# servo-pwm.net
KiCad netlist of a schematic drawn in EAGLE
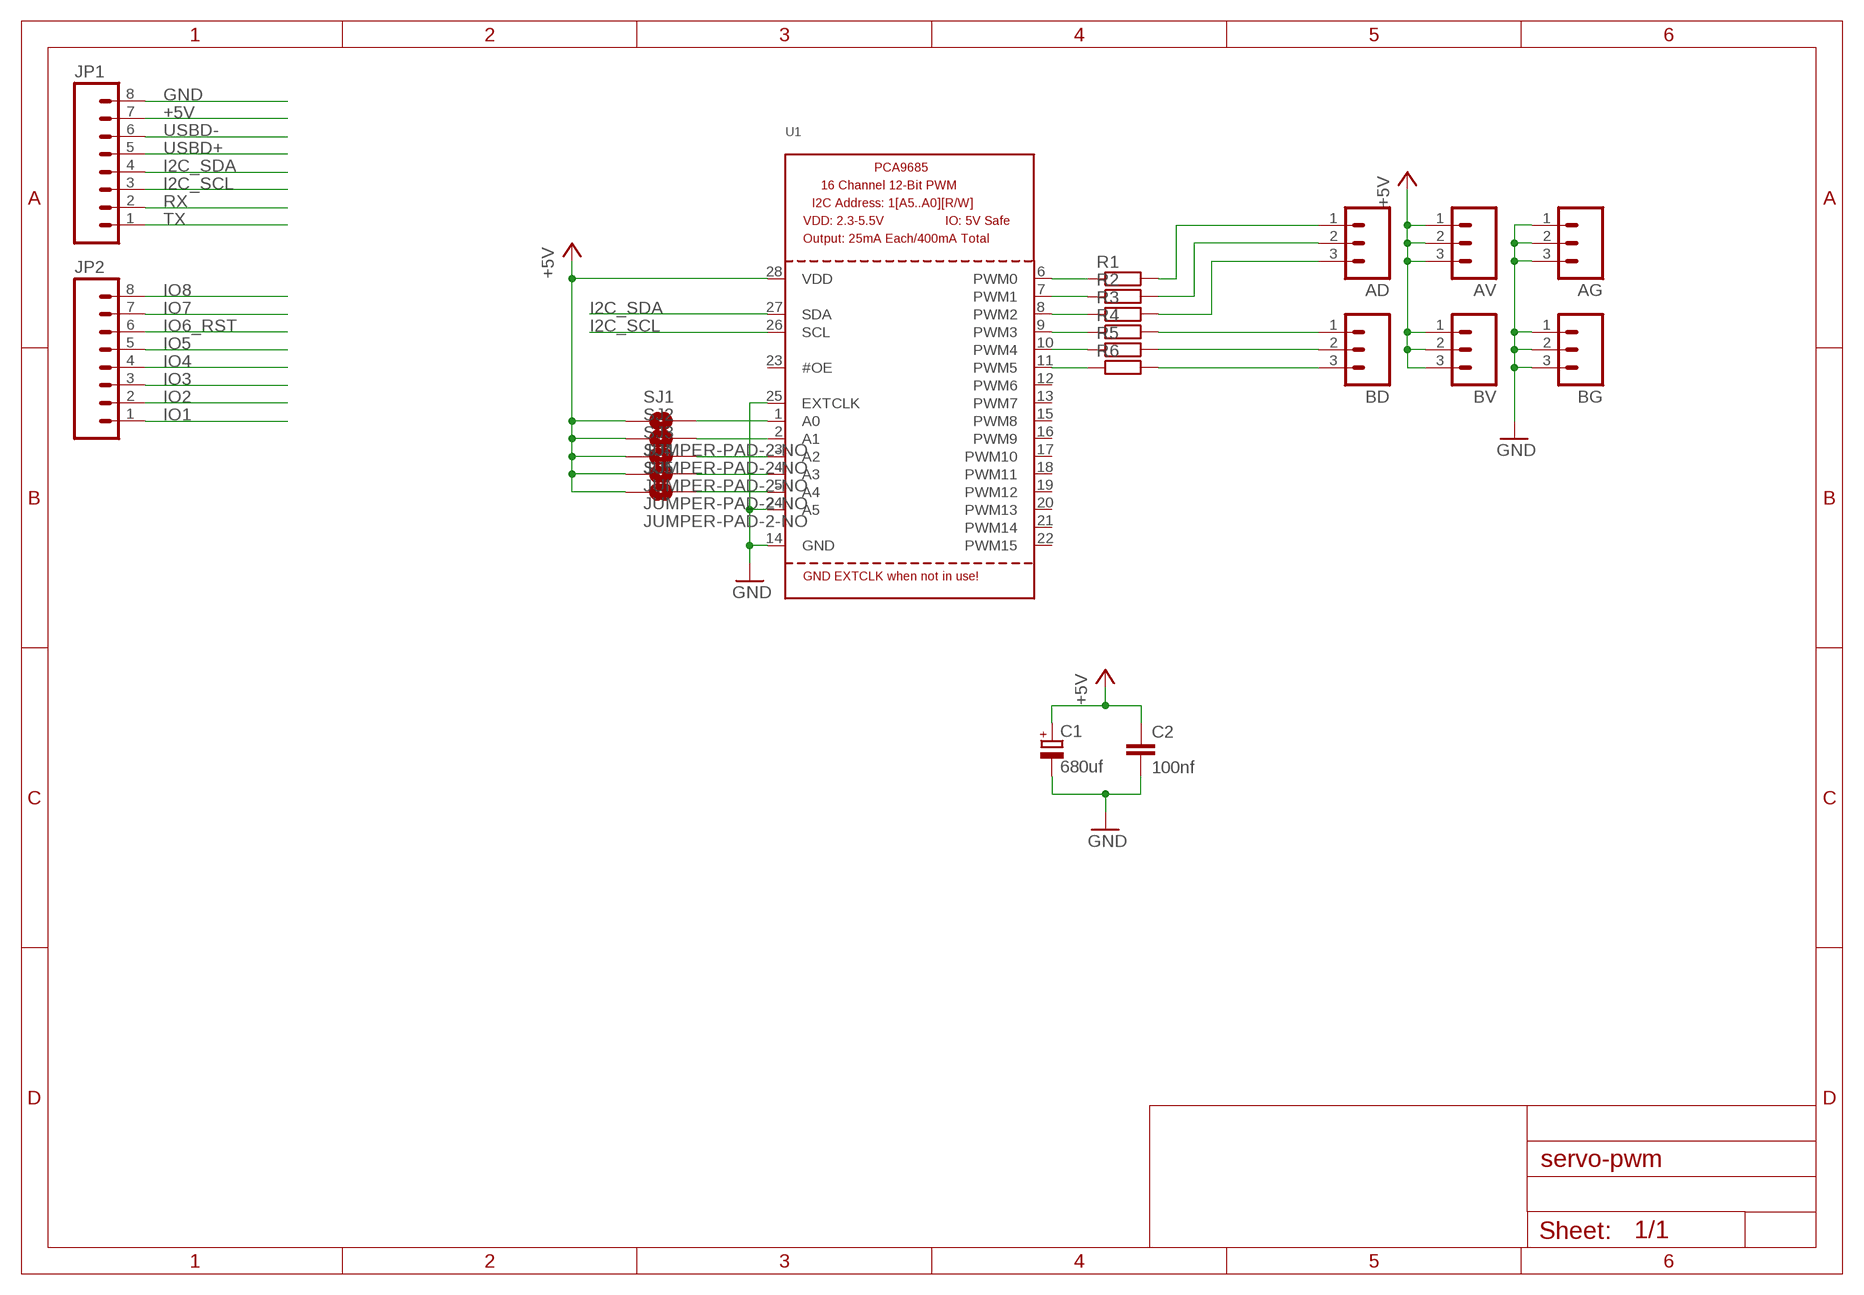
[diagram p0: schematic, sheet 1]

(export (version "E")
  (design (tool "Eeschema 10.0.6"))
  (components
    (comp (ref "AD")
      (value "M03LOCK")
      (footprint "eagle-import:1X03_LOCK")
      (libsource (lib "eagle-import") (part "M03LOCK"))
    )
    (comp (ref "AG")
      (value "M03LOCK")
      (footprint "eagle-import:1X03_LOCK")
      (libsource (lib "eagle-import") (part "M03LOCK"))
    )
    (comp (ref "AV")
      (value "M03LOCK")
      (footprint "eagle-import:1X03_LOCK")
      (libsource (lib "eagle-import") (part "M03LOCK"))
    )
    (comp (ref "BD")
      (value "M03LOCK")
      (footprint "eagle-import:1X03_LOCK")
      (libsource (lib "eagle-import") (part "M03LOCK"))
    )
    (comp (ref "BG")
      (value "M03LOCK")
      (footprint "eagle-import:1X03_LOCK")
      (libsource (lib "eagle-import") (part "M03LOCK"))
    )
    (comp (ref "BV")
      (value "M03LOCK")
      (footprint "eagle-import:1X03_LOCK")
      (libsource (lib "eagle-import") (part "M03LOCK"))
    )
    (comp (ref "C1")
      (value "680uf")
      (footprint "eagle-import:E2,5-7")
      (libsource (lib "eagle-import") (part "CPOL-EUE2.5-7"))
    )
    (comp (ref "C2")
      (value "100nf")
      (footprint "eagle-import:C025-030X050")
      (libsource (lib "eagle-import") (part "C-EU025-030X050"))
    )
    (comp (ref "JP1")
      (value "M081X08")
      (footprint "eagle-import:1X08")
      (libsource (lib "eagle-import") (part "M081X08"))
    )
    (comp (ref "JP2")
      (value "M081X08")
      (footprint "eagle-import:1X08")
      (libsource (lib "eagle-import") (part "M081X08"))
    )
    (comp (ref "R1")
      (value "R-EU_M0805")
      (footprint "eagle-import:M0805")
      (libsource (lib "eagle-import") (part "R-EU_M0805"))
    )
    (comp (ref "R2")
      (value "R-EU_M0805")
      (footprint "eagle-import:M0805")
      (libsource (lib "eagle-import") (part "R-EU_M0805"))
    )
    (comp (ref "R3")
      (value "R-EU_M0805")
      (footprint "eagle-import:M0805")
      (libsource (lib "eagle-import") (part "R-EU_M0805"))
    )
    (comp (ref "R4")
      (value "R-EU_M0805")
      (footprint "eagle-import:M0805")
      (libsource (lib "eagle-import") (part "R-EU_M0805"))
    )
    (comp (ref "R5")
      (value "R-EU_M0805")
      (footprint "eagle-import:M0805")
      (libsource (lib "eagle-import") (part "R-EU_M0805"))
    )
    (comp (ref "R6")
      (value "R-EU_M0805")
      (footprint "eagle-import:M0805")
      (libsource (lib "eagle-import") (part "R-EU_M0805"))
    )
    (comp (ref "SJ1")
      (value "JUMPER-PAD-2-NO")
      (footprint "eagle-import:PAD-JUMPER-2-NO_NO_SILK")
      (libsource (lib "eagle-import") (part "JUMPER-PAD-2-NO"))
    )
    (comp (ref "SJ2")
      (value "JUMPER-PAD-2-NO")
      (footprint "eagle-import:PAD-JUMPER-2-NO_NO_SILK")
      (libsource (lib "eagle-import") (part "JUMPER-PAD-2-NO"))
    )
    (comp (ref "SJ3")
      (value "JUMPER-PAD-2-NO")
      (footprint "eagle-import:PAD-JUMPER-2-NO_NO_SILK")
      (libsource (lib "eagle-import") (part "JUMPER-PAD-2-NO"))
    )
    (comp (ref "SJ4")
      (value "JUMPER-PAD-2-NO")
      (footprint "eagle-import:PAD-JUMPER-2-NO_NO_SILK")
      (libsource (lib "eagle-import") (part "JUMPER-PAD-2-NO"))
    )
    (comp (ref "SJ5")
      (value "JUMPER-PAD-2-NO")
      (footprint "eagle-import:PAD-JUMPER-2-NO_NO_SILK")
      (libsource (lib "eagle-import") (part "JUMPER-PAD-2-NO"))
    )
    (comp (ref "U1")
      (value "PCA9685")
      (footprint "eagle-import:TSSOP28")
      (libsource (lib "eagle-import") (part "PCA9685"))
    )
  )
  (nets
    (net (code "1") (name "+5V") (class "Default")
      (node (ref "AV") (pin "1") (pinfunction "1_1") (pintype "passive"))
      (node (ref "AV") (pin "2") (pinfunction "2_2") (pintype "passive"))
      (node (ref "AV") (pin "3") (pinfunction "3_3") (pintype "passive"))
      (node (ref "BV") (pin "1") (pinfunction "1_1") (pintype "passive"))
      (node (ref "BV") (pin "2") (pinfunction "2_2") (pintype "passive"))
      (node (ref "BV") (pin "3") (pinfunction "3_3") (pintype "passive"))
      (node (ref "C1") (pin "+") (pinfunction "+_+") (pintype "passive"))
      (node (ref "C2") (pin "1") (pinfunction "1_1") (pintype "passive"))
      (node (ref "JP1") (pin "7") (pinfunction "7_7") (pintype "passive"))
      (node (ref "SJ1") (pin "1") (pinfunction "1_1") (pintype "passive"))
      (node (ref "SJ2") (pin "1") (pinfunction "1_1") (pintype "passive"))
      (node (ref "SJ3") (pin "1") (pinfunction "1_1") (pintype "passive"))
      (node (ref "SJ4") (pin "1") (pinfunction "1_1") (pintype "passive"))
      (node (ref "SJ5") (pin "1") (pinfunction "1_1") (pintype "passive"))
      (node (ref "U1") (pin "28") (pinfunction "VDD_28") (pintype "power_in"))
    )
    (net (code "2") (name "/I2C_SCL") (class "Default")
      (node (ref "JP1") (pin "3") (pinfunction "3_3") (pintype "passive"))
      (node (ref "U1") (pin "26") (pinfunction "SCL_26") (pintype "bidirectional"))
    )
    (net (code "3") (name "/I2C_SDA") (class "Default")
      (node (ref "JP1") (pin "4") (pinfunction "4_4") (pintype "passive"))
      (node (ref "U1") (pin "27") (pinfunction "SDA_27") (pintype "bidirectional"))
    )
    (net (code "4") (name "/IO1") (class "Default")
      (node (ref "JP2") (pin "1") (pinfunction "1_1") (pintype "passive"))
    )
    (net (code "5") (name "/IO2") (class "Default")
      (node (ref "JP2") (pin "2") (pinfunction "2_2") (pintype "passive"))
    )
    (net (code "6") (name "/IO3") (class "Default")
      (node (ref "JP2") (pin "3") (pinfunction "3_3") (pintype "passive"))
    )
    (net (code "7") (name "/IO4") (class "Default")
      (node (ref "JP2") (pin "4") (pinfunction "4_4") (pintype "passive"))
    )
    (net (code "8") (name "/IO5") (class "Default")
      (node (ref "JP2") (pin "5") (pinfunction "5_5") (pintype "passive"))
    )
    (net (code "9") (name "/IO6_RST") (class "Default")
      (node (ref "JP2") (pin "6") (pinfunction "6_6") (pintype "passive"))
    )
    (net (code "10") (name "/IO7") (class "Default")
      (node (ref "JP2") (pin "7") (pinfunction "7_7") (pintype "passive"))
    )
    (net (code "11") (name "/IO8") (class "Default")
      (node (ref "JP2") (pin "8") (pinfunction "8_8") (pintype "passive"))
    )
    (net (code "12") (name "/RX") (class "Default")
      (node (ref "JP1") (pin "2") (pinfunction "2_2") (pintype "passive"))
    )
    (net (code "13") (name "/TX") (class "Default")
      (node (ref "JP1") (pin "1") (pinfunction "1_1") (pintype "passive"))
    )
    (net (code "14") (name "/USBD+") (class "Default")
      (node (ref "JP1") (pin "5") (pinfunction "5_5") (pintype "passive"))
    )
    (net (code "15") (name "/USBD-") (class "Default")
      (node (ref "JP1") (pin "6") (pinfunction "6_6") (pintype "passive"))
    )
    (net (code "16") (name "GND") (class "Default")
      (node (ref "AG") (pin "1") (pinfunction "1_1") (pintype "passive"))
      (node (ref "AG") (pin "2") (pinfunction "2_2") (pintype "passive"))
      (node (ref "AG") (pin "3") (pinfunction "3_3") (pintype "passive"))
      (node (ref "BG") (pin "1") (pinfunction "1_1") (pintype "passive"))
      (node (ref "BG") (pin "2") (pinfunction "2_2") (pintype "passive"))
      (node (ref "BG") (pin "3") (pinfunction "3_3") (pintype "passive"))
      (node (ref "C1") (pin "-") (pinfunction "-_-") (pintype "passive"))
      (node (ref "C2") (pin "2") (pinfunction "2_2") (pintype "passive"))
      (node (ref "JP1") (pin "8") (pinfunction "8_8") (pintype "passive"))
      (node (ref "U1") (pin "14") (pinfunction "GND_14") (pintype "power_in"))
      (node (ref "U1") (pin "24") (pinfunction "A5_24") (pintype "bidirectional"))
      (node (ref "U1") (pin "25") (pinfunction "EXTCLK_25") (pintype "input"))
    )
    (net (code "17") (name "Net-(AD-Pad1)") (class "Default")
      (node (ref "AD") (pin "1") (pinfunction "1_1") (pintype "passive"))
      (node (ref "R1") (pin "2") (pinfunction "2_2") (pintype "passive"))
    )
    (net (code "18") (name "Net-(AD-Pad2)") (class "Default")
      (node (ref "AD") (pin "2") (pinfunction "2_2") (pintype "passive"))
      (node (ref "R2") (pin "2") (pinfunction "2_2") (pintype "passive"))
    )
    (net (code "19") (name "Net-(AD-Pad3)") (class "Default")
      (node (ref "AD") (pin "3") (pinfunction "3_3") (pintype "passive"))
      (node (ref "R3") (pin "2") (pinfunction "2_2") (pintype "passive"))
    )
    (net (code "20") (name "Net-(BD-Pad1)") (class "Default")
      (node (ref "BD") (pin "1") (pinfunction "1_1") (pintype "passive"))
      (node (ref "R4") (pin "2") (pinfunction "2_2") (pintype "passive"))
    )
    (net (code "21") (name "Net-(BD-Pad2)") (class "Default")
      (node (ref "BD") (pin "2") (pinfunction "2_2") (pintype "passive"))
      (node (ref "R5") (pin "2") (pinfunction "2_2") (pintype "passive"))
    )
    (net (code "22") (name "Net-(BD-Pad3)") (class "Default")
      (node (ref "BD") (pin "3") (pinfunction "3_3") (pintype "passive"))
      (node (ref "R6") (pin "2") (pinfunction "2_2") (pintype "passive"))
    )
    (net (code "23") (name "Net-(U1-A0)") (class "Default")
      (node (ref "SJ1") (pin "2") (pinfunction "2_2") (pintype "passive"))
      (node (ref "U1") (pin "1") (pinfunction "A0_1") (pintype "bidirectional"))
    )
    (net (code "24") (name "Net-(U1-A1)") (class "Default")
      (node (ref "SJ2") (pin "2") (pinfunction "2_2") (pintype "passive"))
      (node (ref "U1") (pin "2") (pinfunction "A1_2") (pintype "bidirectional"))
    )
    (net (code "25") (name "Net-(U1-A2)") (class "Default")
      (node (ref "SJ3") (pin "2") (pinfunction "2_2") (pintype "passive"))
      (node (ref "U1") (pin "3") (pinfunction "A2_3") (pintype "bidirectional"))
    )
    (net (code "26") (name "Net-(U1-A3)") (class "Default")
      (node (ref "SJ4") (pin "2") (pinfunction "2_2") (pintype "passive"))
      (node (ref "U1") (pin "4") (pinfunction "A3_4") (pintype "bidirectional"))
    )
    (net (code "27") (name "Net-(U1-A4)") (class "Default")
      (node (ref "SJ5") (pin "2") (pinfunction "2_2") (pintype "passive"))
      (node (ref "U1") (pin "5") (pinfunction "A4_5") (pintype "bidirectional"))
    )
    (net (code "28") (name "Net-(U1-PWM0)") (class "Default")
      (node (ref "R1") (pin "1") (pinfunction "1_1") (pintype "passive"))
      (node (ref "U1") (pin "6") (pinfunction "PWM0_6") (pintype "output"))
    )
    (net (code "29") (name "Net-(U1-PWM1)") (class "Default")
      (node (ref "R2") (pin "1") (pinfunction "1_1") (pintype "passive"))
      (node (ref "U1") (pin "7") (pinfunction "PWM1_7") (pintype "output"))
    )
    (net (code "30") (name "Net-(U1-PWM2)") (class "Default")
      (node (ref "R3") (pin "1") (pinfunction "1_1") (pintype "passive"))
      (node (ref "U1") (pin "8") (pinfunction "PWM2_8") (pintype "output"))
    )
    (net (code "31") (name "Net-(U1-PWM3)") (class "Default")
      (node (ref "R4") (pin "1") (pinfunction "1_1") (pintype "passive"))
      (node (ref "U1") (pin "9") (pinfunction "PWM3_9") (pintype "output"))
    )
    (net (code "32") (name "Net-(U1-PWM4)") (class "Default")
      (node (ref "R5") (pin "1") (pinfunction "1_1") (pintype "passive"))
      (node (ref "U1") (pin "10") (pinfunction "PWM4_10") (pintype "output"))
    )
    (net (code "33") (name "Net-(U1-PWM5)") (class "Default")
      (node (ref "R6") (pin "1") (pinfunction "1_1") (pintype "passive"))
      (node (ref "U1") (pin "11") (pinfunction "PWM5_11") (pintype "output"))
    )
    (net (code "34") (name "unconnected-(U1-#OE-Pad23)") (class "Default")
      (node (ref "U1") (pin "23") (pinfunction "#OE_23") (pintype "input"))
    )
    (net (code "35") (name "unconnected-(U1-PWM6-Pad12)") (class "Default")
      (node (ref "U1") (pin "12") (pinfunction "PWM6_12") (pintype "output"))
    )
    (net (code "36") (name "unconnected-(U1-PWM7-Pad13)") (class "Default")
      (node (ref "U1") (pin "13") (pinfunction "PWM7_13") (pintype "output"))
    )
    (net (code "37") (name "unconnected-(U1-PWM8-Pad15)") (class "Default")
      (node (ref "U1") (pin "15") (pinfunction "PWM8_15") (pintype "output"))
    )
    (net (code "38") (name "unconnected-(U1-PWM9-Pad16)") (class "Default")
      (node (ref "U1") (pin "16") (pinfunction "PWM9_16") (pintype "output"))
    )
    (net (code "39") (name "unconnected-(U1-PWM10-Pad17)") (class "Default")
      (node (ref "U1") (pin "17") (pinfunction "PWM10_17") (pintype "output"))
    )
    (net (code "40") (name "unconnected-(U1-PWM11-Pad18)") (class "Default")
      (node (ref "U1") (pin "18") (pinfunction "PWM11_18") (pintype "output"))
    )
    (net (code "41") (name "unconnected-(U1-PWM12-Pad19)") (class "Default")
      (node (ref "U1") (pin "19") (pinfunction "PWM12_19") (pintype "output"))
    )
    (net (code "42") (name "unconnected-(U1-PWM13-Pad20)") (class "Default")
      (node (ref "U1") (pin "20") (pinfunction "PWM13_20") (pintype "output"))
    )
    (net (code "43") (name "unconnected-(U1-PWM14-Pad21)") (class "Default")
      (node (ref "U1") (pin "21") (pinfunction "PWM14_21") (pintype "output"))
    )
    (net (code "44") (name "unconnected-(U1-PWM15-Pad22)") (class "Default")
      (node (ref "U1") (pin "22") (pinfunction "PWM15_22") (pintype "output"))
    )
  )
)
